# MIXR_Processing_-_STM32_USB-UART_Convert.net
KiCad netlist of a schematic drawn in Altium Designer
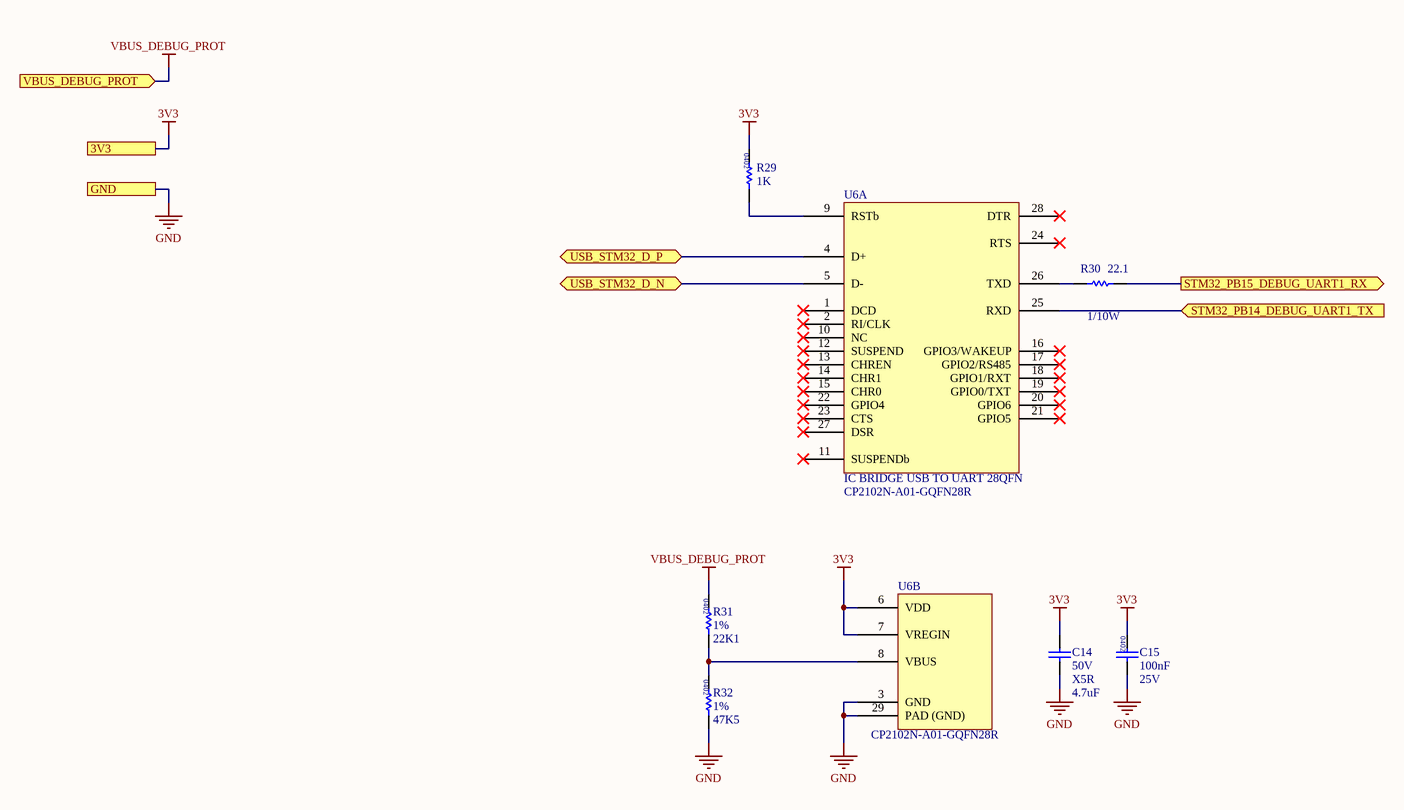
[diagram p0: MIXR Processing - STM32 USB-UART Converter.SchDoc]

(export (version "E")
  (design (tool "Eeschema 10.0.6"))
  (components
    (comp (ref "C14")
      (value "4.7uF")
      (footprint "CAP, 0805")
      (description "4.7µF ±20% 50V Ceramic Capacitor X5R 0805 (2012 Metric)")
      (fields
        (field (name "TOLERANCE") "±20%")
        (field (name "VOLTAGE - RATED") "50V")
        (field (name "TEMPERATURE COEFFICIENT") "X5R")
        (field (name "Comment") "CAP CER 4.7UF 50V 10% X5R 0805")
      )
      (libsource (lib "Schematic Diagrams") (part "CAP CER 4.7UF 50V 10% X5R 0805"))
    )
    (comp (ref "C15")
      (value "CAP CER 0.1UF 16V X7R 0402")
      (footprint "CAP 0402")
      (description "Cap Ceramic 0.1uF 25V X7R 10% SMD 0402 125C Paper T/R")
      (fields
        (field (name "TOLERANCE") "10%")
        (field (name "CAPACITANCE") "100nF")
        (field (name "VOLTAGE") "25V")
        (field (name "MANUFACTURER") "Murata")
      )
      (libsource (lib "Schematic Diagrams") (part "CAP CER 0.1UF 16V X7R 0402"))
    )
    (comp (ref "R29")
      (value "RES 1K OHM 0.1% 1/16W 0402")
      (footprint "RES 0402")
      (description "RES SMD 1K OHM 0.1% 1/16W 0402")
      (fields
        (field (name "MANUFACTURER") "Yageo")
        (field (name "MANUFACTURER PART NUMBER") "RT0402BRE071KL")
        (field (name "RESISTANCE") "1K")
      )
      (libsource (lib "Schematic Diagrams") (part "RES 1K OHM 0.1% 1/16W 0402"))
    )
    (comp (ref "R30")
      (value "RES 22.1 OHM 1% 1/10W 0603")
      (footprint "RES, 0603")
      (description "22.1 Ohm ±1% 0.1W, 1/10W Chip Resistor 0603 (1608 Metric) Moisture Resistant Thick Film")
      (fields
        (field (name "TOLERANCE") "±1%")
        (field (name "RESISTANCE") "22.1")
        (field (name "POWER") "1/10W")
      )
      (libsource (lib "Schematic Diagrams") (part "RES 22.1 OHM 1% 1/10W 0603"))
    )
    (comp (ref "R31")
      (value "RES 22.1K OHM 1% 1/16W 0402")
      (footprint "RES 0402")
      (description "RES SMD 22.1K OHM 1% 1/16W 0402")
      (fields
        (field (name "MANUFACTURER") "Stackpole Electronics")
        (field (name "MANUFACTURER PART NUMBER") "RMCF0402FT22K1")
        (field (name "TOLERANCE") "1%")
        (field (name "RESISTANCE") "22K1")
      )
      (libsource (lib "Schematic Diagrams") (part "RES 22.1K OHM 1% 1/16W 0402"))
    )
    (comp (ref "R32")
      (value "RES 47.5K OHM 1% 1/16W 0402")
      (footprint "RES 0402")
      (description "RES SMD 47.5K OHM 1% 1/16W 0402")
      (fields
        (field (name "MANUFACTURER") "Yageo")
        (field (name "MANUFACTURER PART NUMBER") "RC0402FR-0747K5L")
        (field (name "TOLERANCE") "1%")
        (field (name "RESISTANCE") "47K5")
      )
      (libsource (lib "Schematic Diagrams") (part "RES 47.5K OHM 1% 1/16W 0402"))
    )
    (comp (ref "U6")
      (value "IC BRIDGE USB TO UART 28QFN")
      (footprint "QFN50P500X500X80_HS-29M")
      (fields
        (field (name "MANUFACTURER") "Silicon Labs")
        (field (name "MANUFACTURER PART NUMBER") "CP2102N-A01-GQFN28R")
      )
      (libsource (lib "Schematic Diagrams") (part "IC BRIDGE USB TO UART 28QFN"))
    )
  )
  (nets
    (net (code "1") (name "/STM32_PB14_DEBUG_UART1_TX") (class "Default")
      (node (ref "U6") (pin "25") (pinfunction "RXD_25") (pintype "passive"))
    )
    (net (code "2") (name "/STM32_PB15_DEBUG_UART1_RX") (class "Default")
      (node (ref "R30") (pin "2") (pinfunction "2_2") (pintype "passive"))
    )
    (net (code "3") (name "/USB_STM32_D_N") (class "Default")
      (node (ref "U6") (pin "5") (pinfunction "D-_5") (pintype "passive"))
    )
    (net (code "4") (name "/USB_STM32_D_P") (class "Default")
      (node (ref "U6") (pin "4") (pinfunction "D+_4") (pintype "passive"))
    )
    (net (code "5") (name "3V3") (class "Default")
      (node (ref "C14") (pin "1") (pinfunction "1_1") (pintype "passive"))
      (node (ref "C15") (pin "1") (pinfunction "1_1") (pintype "passive"))
      (node (ref "R29") (pin "1") (pinfunction "1_1") (pintype "passive"))
      (node (ref "U6") (pin "6") (pinfunction "VDD_6") (pintype "passive"))
      (node (ref "U6") (pin "7") (pinfunction "VREGIN_7") (pintype "passive"))
    )
    (net (code "6") (name "GND") (class "Default")
      (node (ref "C14") (pin "2") (pinfunction "2_2") (pintype "passive"))
      (node (ref "C15") (pin "2") (pinfunction "2_2") (pintype "passive"))
      (node (ref "R32") (pin "2") (pinfunction "2_2") (pintype "passive"))
      (node (ref "U6") (pin "29") (pinfunction "PAD_(GND)_29") (pintype "passive"))
      (node (ref "U6") (pin "3") (pinfunction "GND_3") (pintype "passive"))
    )
    (net (code "7") (name "Net-(U6A-RSTb)") (class "Default")
      (node (ref "R29") (pin "2") (pinfunction "2_2") (pintype "passive"))
      (node (ref "U6") (pin "9") (pinfunction "RSTb_9") (pintype "passive"))
    )
    (net (code "8") (name "Net-(U6A-TXD)") (class "Default")
      (node (ref "R30") (pin "1") (pinfunction "1_1") (pintype "passive"))
      (node (ref "U6") (pin "26") (pinfunction "TXD_26") (pintype "passive"))
    )
    (net (code "9") (name "Net-(U6B-VBUS)") (class "Default")
      (node (ref "R31") (pin "2") (pinfunction "2_2") (pintype "passive"))
      (node (ref "R32") (pin "1") (pinfunction "1_1") (pintype "passive"))
      (node (ref "U6") (pin "8") (pinfunction "VBUS_8") (pintype "passive"))
    )
    (net (code "10") (name "VBUS_DEBUG_PROT") (class "Default")
      (node (ref "R31") (pin "1") (pinfunction "1_1") (pintype "passive"))
    )
    (net (code "11") (name "unconnected-(U6A-CHR0-Pad15)") (class "Default")
      (node (ref "U6") (pin "15") (pinfunction "CHR0_15") (pintype "passive+no_connect"))
    )
    (net (code "12") (name "unconnected-(U6A-CHR1-Pad14)") (class "Default")
      (node (ref "U6") (pin "14") (pinfunction "CHR1_14") (pintype "passive+no_connect"))
    )
    (net (code "13") (name "unconnected-(U6A-CHREN-Pad13)") (class "Default")
      (node (ref "U6") (pin "13") (pinfunction "CHREN_13") (pintype "passive+no_connect"))
    )
    (net (code "14") (name "unconnected-(U6A-CTS-Pad23)") (class "Default")
      (node (ref "U6") (pin "23") (pinfunction "CTS_23") (pintype "passive+no_connect"))
    )
    (net (code "15") (name "unconnected-(U6A-DCD-Pad1)") (class "Default")
      (node (ref "U6") (pin "1") (pinfunction "DCD_1") (pintype "passive+no_connect"))
    )
    (net (code "16") (name "unconnected-(U6A-DSR-Pad27)") (class "Default")
      (node (ref "U6") (pin "27") (pinfunction "DSR_27") (pintype "passive+no_connect"))
    )
    (net (code "17") (name "unconnected-(U6A-DTR-Pad28)") (class "Default")
      (node (ref "U6") (pin "28") (pinfunction "DTR_28") (pintype "passive+no_connect"))
    )
    (net (code "18") (name "unconnected-(U6A-GPIO0{slash}TXT-Pad19)") (class "Default")
      (node (ref "U6") (pin "19") (pinfunction "GPIO0/TXT_19") (pintype "passive+no_connect"))
    )
    (net (code "19") (name "unconnected-(U6A-GPIO1{slash}RXT-Pad18)") (class "Default")
      (node (ref "U6") (pin "18") (pinfunction "GPIO1/RXT_18") (pintype "passive+no_connect"))
    )
    (net (code "20") (name "unconnected-(U6A-GPIO2{slash}RS485-Pad17)") (class "Default")
      (node (ref "U6") (pin "17") (pinfunction "GPIO2/RS485_17") (pintype "passive+no_connect"))
    )
    (net (code "21") (name "unconnected-(U6A-GPIO3{slash}WAKEUP-Pad16)") (class "Default")
      (node (ref "U6") (pin "16") (pinfunction "GPIO3/WAKEUP_16") (pintype "passive+no_connect"))
    )
    (net (code "22") (name "unconnected-(U6A-GPIO4-Pad22)") (class "Default")
      (node (ref "U6") (pin "22") (pinfunction "GPIO4_22") (pintype "passive+no_connect"))
    )
    (net (code "23") (name "unconnected-(U6A-GPIO5-Pad21)") (class "Default")
      (node (ref "U6") (pin "21") (pinfunction "GPIO5_21") (pintype "passive+no_connect"))
    )
    (net (code "24") (name "unconnected-(U6A-GPIO6-Pad20)") (class "Default")
      (node (ref "U6") (pin "20") (pinfunction "GPIO6_20") (pintype "passive+no_connect"))
    )
    (net (code "25") (name "unconnected-(U6A-NC-Pad10)") (class "Default")
      (node (ref "U6") (pin "10") (pinfunction "NC_10") (pintype "passive+no_connect"))
    )
    (net (code "26") (name "unconnected-(U6A-RI{slash}CLK-Pad2)") (class "Default")
      (node (ref "U6") (pin "2") (pinfunction "RI/CLK_2") (pintype "passive+no_connect"))
    )
    (net (code "27") (name "unconnected-(U6A-RTS-Pad24)") (class "Default")
      (node (ref "U6") (pin "24") (pinfunction "RTS_24") (pintype "passive+no_connect"))
    )
    (net (code "28") (name "unconnected-(U6A-SUSPEND-Pad12)") (class "Default")
      (node (ref "U6") (pin "12") (pinfunction "SUSPEND_12") (pintype "passive+no_connect"))
    )
    (net (code "29") (name "unconnected-(U6A-SUSPENDb-Pad11)") (class "Default")
      (node (ref "U6") (pin "11") (pinfunction "SUSPENDb_11") (pintype "passive+no_connect"))
    )
  )
)
